# schuifregister.net
KiCad netlist of a schematic drawn in EAGLE
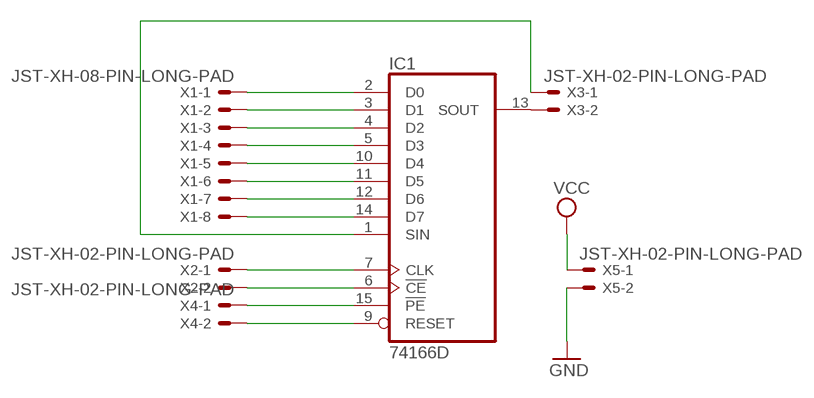
[diagram p0: schematic, sheet 1]

(export (version "E")
  (design (tool "Eeschema 10.0.6"))
  (components
    (comp (ref "IC1")
      (value "74166D")
      (footprint "eagle-import:SO16")
      (libsource (lib "eagle-import") (part "74166D"))
    )
    (comp (ref "X1")
      (value "JST-XH-08-PIN-LONG-PAD")
      (footprint "eagle-import:JST-XH-08-PACKAGE-LONG-PAD")
      (libsource (lib "eagle-import") (part "JST-XH-08-PIN-LONG-PAD"))
    )
    (comp (ref "X2")
      (value "JST-XH-02-PIN-LONG-PAD")
      (footprint "eagle-import:JST-XH-02-PACKAGE-LONG-PAD")
      (libsource (lib "eagle-import") (part "JST-XH-02-PIN-LONG-PAD"))
    )
    (comp (ref "X3")
      (value "JST-XH-02-PIN-LONG-PAD")
      (footprint "eagle-import:JST-XH-02-PACKAGE-LONG-PAD")
      (libsource (lib "eagle-import") (part "JST-XH-02-PIN-LONG-PAD"))
    )
    (comp (ref "X4")
      (value "JST-XH-02-PIN-LONG-PAD")
      (footprint "eagle-import:JST-XH-02-PACKAGE-LONG-PAD")
      (libsource (lib "eagle-import") (part "JST-XH-02-PIN-LONG-PAD"))
    )
    (comp (ref "X5")
      (value "JST-XH-02-PIN-LONG-PAD")
      (footprint "eagle-import:JST-XH-02-PACKAGE-LONG-PAD")
      (libsource (lib "eagle-import") (part "JST-XH-02-PIN-LONG-PAD"))
    )
  )
  (nets
    (net (code "1") (name "GND") (class "Default")
      (node (ref "X5") (pin "2") (pinfunction "S_2") (pintype "passive"))
    )
    (net (code "2") (name "Net-(IC1A-CLK)") (class "Default")
      (node (ref "IC1") (pin "7") (pinfunction "CLK_7") (pintype "input"))
      (node (ref "X2") (pin "1") (pinfunction "S_1") (pintype "passive"))
    )
    (net (code "3") (name "Net-(IC1A-D0)") (class "Default")
      (node (ref "IC1") (pin "2") (pinfunction "D0_2") (pintype "input"))
      (node (ref "X1") (pin "1") (pinfunction "S_1") (pintype "passive"))
    )
    (net (code "4") (name "Net-(IC1A-D1)") (class "Default")
      (node (ref "IC1") (pin "3") (pinfunction "D1_3") (pintype "input"))
      (node (ref "X1") (pin "2") (pinfunction "S_2") (pintype "passive"))
    )
    (net (code "5") (name "Net-(IC1A-D2)") (class "Default")
      (node (ref "IC1") (pin "4") (pinfunction "D2_4") (pintype "input"))
      (node (ref "X1") (pin "3") (pinfunction "S_3") (pintype "passive"))
    )
    (net (code "6") (name "Net-(IC1A-D3)") (class "Default")
      (node (ref "IC1") (pin "5") (pinfunction "D3_5") (pintype "input"))
      (node (ref "X1") (pin "4") (pinfunction "S_4") (pintype "passive"))
    )
    (net (code "7") (name "Net-(IC1A-D4)") (class "Default")
      (node (ref "IC1") (pin "10") (pinfunction "D4_10") (pintype "input"))
      (node (ref "X1") (pin "5") (pinfunction "S_5") (pintype "passive"))
    )
    (net (code "8") (name "Net-(IC1A-D5)") (class "Default")
      (node (ref "IC1") (pin "11") (pinfunction "D5_11") (pintype "input"))
      (node (ref "X1") (pin "6") (pinfunction "S_6") (pintype "passive"))
    )
    (net (code "9") (name "Net-(IC1A-D6)") (class "Default")
      (node (ref "IC1") (pin "12") (pinfunction "D6_12") (pintype "input"))
      (node (ref "X1") (pin "7") (pinfunction "S_7") (pintype "passive"))
    )
    (net (code "10") (name "Net-(IC1A-D7)") (class "Default")
      (node (ref "IC1") (pin "14") (pinfunction "D7_14") (pintype "input"))
      (node (ref "X1") (pin "8") (pinfunction "S_8") (pintype "passive"))
    )
    (net (code "11") (name "Net-(IC1A-RESET)") (class "Default")
      (node (ref "IC1") (pin "9") (pinfunction "RESET_9") (pintype "input"))
      (node (ref "X4") (pin "2") (pinfunction "S_2") (pintype "passive"))
    )
    (net (code "12") (name "Net-(IC1A-SIN)") (class "Default")
      (node (ref "IC1") (pin "1") (pinfunction "SIN_1") (pintype "input"))
      (node (ref "X3") (pin "1") (pinfunction "S_1") (pintype "passive"))
    )
    (net (code "13") (name "Net-(IC1A-SOUT)") (class "Default")
      (node (ref "IC1") (pin "13") (pinfunction "SOUT_13") (pintype "output"))
      (node (ref "X3") (pin "2") (pinfunction "S_2") (pintype "passive"))
    )
    (net (code "14") (name "Net-(IC1A-~{CE})") (class "Default")
      (node (ref "IC1") (pin "6") (pinfunction "~{CE}_6") (pintype "input"))
      (node (ref "X2") (pin "2") (pinfunction "S_2") (pintype "passive"))
    )
    (net (code "15") (name "Net-(IC1A-~{PE})") (class "Default")
      (node (ref "IC1") (pin "15") (pinfunction "~{PE}_15") (pintype "input"))
      (node (ref "X4") (pin "1") (pinfunction "S_1") (pintype "passive"))
    )
    (net (code "16") (name "VCC") (class "Default")
      (node (ref "X5") (pin "1") (pinfunction "S_1") (pintype "passive"))
    )
  )
)
